# EBN_WPWR_V01.net
KiCad netlist of a schematic drawn in EAGLE
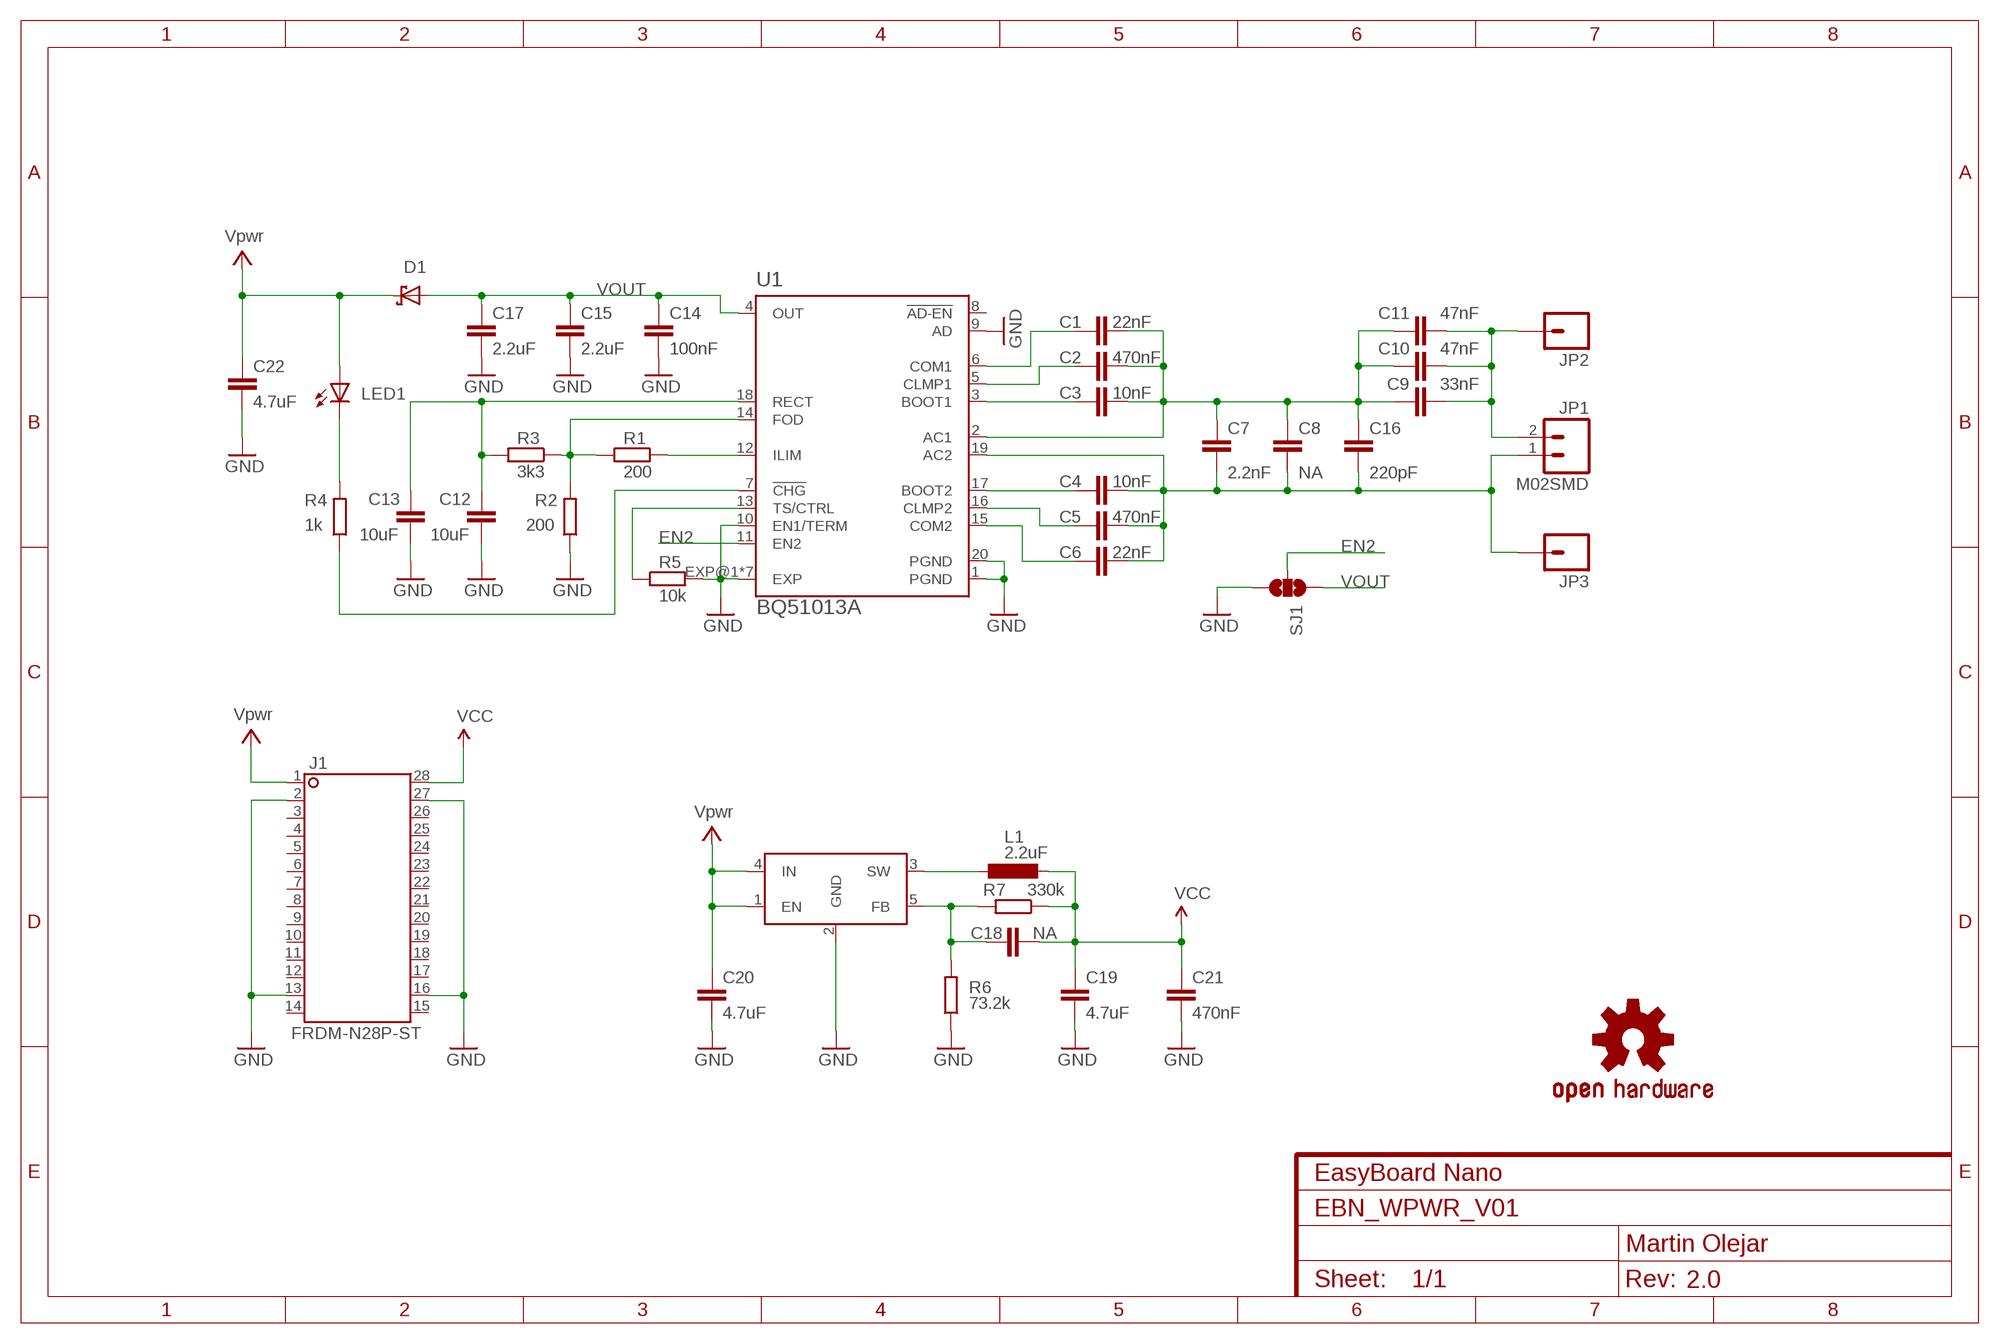
[diagram p0: schematic, sheet 1]

(export (version "E")
  (design (tool "Eeschema 10.0.6"))
  (components
    (comp (ref "C1")
      (value "22nF")
      (footprint "eagle-import:C0603")
      (libsource (lib "eagle-import") (part "C-EUC0603"))
    )
    (comp (ref "C2")
      (value "470nF")
      (footprint "eagle-import:C0603")
      (libsource (lib "eagle-import") (part "C-EUC0603"))
    )
    (comp (ref "C3")
      (value "10nF")
      (footprint "eagle-import:C0603")
      (libsource (lib "eagle-import") (part "C-EUC0603"))
    )
    (comp (ref "C4")
      (value "10nF")
      (footprint "eagle-import:C0603")
      (libsource (lib "eagle-import") (part "C-EUC0603"))
    )
    (comp (ref "C5")
      (value "470nF")
      (footprint "eagle-import:C0603")
      (libsource (lib "eagle-import") (part "C-EUC0603"))
    )
    (comp (ref "C6")
      (value "22nF")
      (footprint "eagle-import:C0603")
      (libsource (lib "eagle-import") (part "C-EUC0603"))
    )
    (comp (ref "C7")
      (value "2.2nF")
      (footprint "eagle-import:C0603")
      (libsource (lib "eagle-import") (part "C-EUC0603"))
    )
    (comp (ref "C8")
      (value "NA")
      (footprint "eagle-import:C0603")
      (libsource (lib "eagle-import") (part "C-EUC0603"))
    )
    (comp (ref "C9")
      (value "33nF")
      (footprint "eagle-import:C0603")
      (libsource (lib "eagle-import") (part "C-EUC0603"))
    )
    (comp (ref "C10")
      (value "47nF")
      (footprint "eagle-import:C0603")
      (libsource (lib "eagle-import") (part "C-EUC0603"))
    )
    (comp (ref "C11")
      (value "47nF")
      (footprint "eagle-import:C0603")
      (libsource (lib "eagle-import") (part "C-EUC0603"))
    )
    (comp (ref "C12")
      (value "10uF")
      (footprint "eagle-import:C0805")
      (libsource (lib "eagle-import") (part "C-EUC0805"))
    )
    (comp (ref "C13")
      (value "10uF")
      (footprint "eagle-import:C0805")
      (libsource (lib "eagle-import") (part "C-EUC0805"))
    )
    (comp (ref "C14")
      (value "100nF")
      (footprint "eagle-import:C0603")
      (libsource (lib "eagle-import") (part "C-EUC0603"))
    )
    (comp (ref "C15")
      (value "2.2uF")
      (footprint "eagle-import:C0603")
      (libsource (lib "eagle-import") (part "C-EUC0603"))
    )
    (comp (ref "C16")
      (value "220pF")
      (footprint "eagle-import:C0603")
      (libsource (lib "eagle-import") (part "C-EUC0603"))
    )
    (comp (ref "C17")
      (value "2.2uF")
      (footprint "eagle-import:C0603")
      (libsource (lib "eagle-import") (part "C-EUC0603"))
    )
    (comp (ref "C18")
      (value "NA")
      (footprint "eagle-import:C0603")
      (libsource (lib "eagle-import") (part "C-EUC0603"))
    )
    (comp (ref "C19")
      (value "4.7uF")
      (footprint "eagle-import:C0603")
      (libsource (lib "eagle-import") (part "C-EUC0603"))
    )
    (comp (ref "C20")
      (value "4.7uF")
      (footprint "eagle-import:C0603")
      (libsource (lib "eagle-import") (part "C-EUC0603"))
    )
    (comp (ref "C21")
      (value "470nF")
      (footprint "eagle-import:C0603")
      (libsource (lib "eagle-import") (part "C-EUC0603"))
    )
    (comp (ref "C22")
      (value "4.7uF")
      (footprint "eagle-import:C0603")
      (libsource (lib "eagle-import") (part "C-EUC0603"))
    )
    (comp (ref "D1")
      (value "PMEG2010BER-SHOTTKY-SOD123FL")
      (footprint "eagle-import:SOD-123FL")
      (libsource (lib "eagle-import") (part "-SHOTTKY-SOD123FLPMEG2010BER"))
    )
    (comp (ref "J1")
      (value "FRDM-N28P-ST")
      (footprint "eagle-import:FRDM-N28P-SHIELD")
      (libsource (lib "eagle-import") (part "FRDM-N28P-ST"))
    )
    (comp (ref "JP1")
      (value "M02SMD")
      (footprint "eagle-import:1X02-1.25MM_SMD")
      (libsource (lib "eagle-import") (part "M02SMD"))
    )
    (comp (ref "JP2")
      (value "M01PTH_LONGPAD")
      (footprint "eagle-import:1X01_LONGPAD")
      (libsource (lib "eagle-import") (part "M01PTH_LONGPAD"))
    )
    (comp (ref "JP3")
      (value "M01PTH_LONGPAD")
      (footprint "eagle-import:1X01_LONGPAD")
      (libsource (lib "eagle-import") (part "M01PTH_LONGPAD"))
    )
    (comp (ref "L1")
      (value "2.2uF")
      (footprint "eagle-import:LPS3015")
      (libsource (lib "eagle-import") (part "L-EULPS3015"))
    )
    (comp (ref "LED1")
      (value "LEDCHIPLED_0603")
      (footprint "eagle-import:CHIPLED_0603")
      (libsource (lib "eagle-import") (part "LEDCHIPLED_0603"))
    )
    (comp (ref "LOGO1")
      (value "OSHW-LOGOS")
      (footprint "eagle-import:OSHW-LOGO-S")
      (libsource (lib "eagle-import") (part "OSHW-LOGOS"))
    )
    (comp (ref "R1")
      (value "200")
      (footprint "eagle-import:R0603")
      (libsource (lib "eagle-import") (part "R-EUR0603"))
    )
    (comp (ref "R2")
      (value "200")
      (footprint "eagle-import:R0603")
      (libsource (lib "eagle-import") (part "R-EUR0603"))
    )
    (comp (ref "R3")
      (value "3k3")
      (footprint "eagle-import:R0603")
      (libsource (lib "eagle-import") (part "R-EUR0603"))
    )
    (comp (ref "R4")
      (value "1k")
      (footprint "eagle-import:R0603")
      (libsource (lib "eagle-import") (part "R-EUR0603"))
    )
    (comp (ref "R5")
      (value "10k")
      (footprint "eagle-import:R0603")
      (libsource (lib "eagle-import") (part "R-EUR0603"))
    )
    (comp (ref "R6")
      (value "73.2k")
      (footprint "eagle-import:R0603")
      (libsource (lib "eagle-import") (part "R-EUR0603"))
    )
    (comp (ref "R7")
      (value "330k")
      (footprint "eagle-import:R0603")
      (libsource (lib "eagle-import") (part "R-EUR0603"))
    )
    (comp (ref "SJ1")
      (value "SJ2W-S")
      (footprint "eagle-import:JUMPER-SMD-S2X")
      (libsource (lib "eagle-import") (part "SJ2W-S"))
    )
    (comp (ref "U$1")
      (value "MP215P")
      (footprint "eagle-import:SOT23-5L")
      (libsource (lib "eagle-import") (part "MP215P"))
    )
    (comp (ref "U1")
      (value "BQ51013A")
      (footprint "eagle-import:RHL_R-VQFN-N20")
      (libsource (lib "eagle-import") (part "BQ51013A"))
    )
  )
  (nets
    (net (code "1") (name "/EN2") (class "Default")
      (node (ref "SJ1") (pin "2") (pinfunction "2_2") (pintype "passive"))
      (node (ref "U1") (pin "11") (pinfunction "EN2_11") (pintype "input"))
    )
    (net (code "2") (name "/VOUT") (class "Default")
      (node (ref "C14") (pin "2") (pinfunction "2_2") (pintype "passive"))
      (node (ref "C15") (pin "2") (pinfunction "2_2") (pintype "passive"))
      (node (ref "C17") (pin "2") (pinfunction "2_2") (pintype "passive"))
      (node (ref "D1") (pin "A") (pinfunction "A_A") (pintype "passive"))
      (node (ref "SJ1") (pin "1") (pinfunction "1_1") (pintype "passive"))
      (node (ref "U1") (pin "4") (pinfunction "OUT_4") (pintype "output"))
    )
    (net (code "3") (name "GND") (class "Default")
      (node (ref "C12") (pin "1") (pinfunction "1_1") (pintype "passive"))
      (node (ref "C13") (pin "1") (pinfunction "1_1") (pintype "passive"))
      (node (ref "C14") (pin "1") (pinfunction "1_1") (pintype "passive"))
      (node (ref "C15") (pin "1") (pinfunction "1_1") (pintype "passive"))
      (node (ref "C17") (pin "1") (pinfunction "1_1") (pintype "passive"))
      (node (ref "C19") (pin "1") (pinfunction "1_1") (pintype "passive"))
      (node (ref "C20") (pin "1") (pinfunction "1_1") (pintype "passive"))
      (node (ref "C21") (pin "1") (pinfunction "1_1") (pintype "passive"))
      (node (ref "C22") (pin "1") (pinfunction "1_1") (pintype "passive"))
      (node (ref "J1") (pin "13") (pinfunction "13_13") (pintype "passive"))
      (node (ref "J1") (pin "16") (pinfunction "16_16") (pintype "passive"))
      (node (ref "J1") (pin "2") (pinfunction "2_2") (pintype "passive"))
      (node (ref "J1") (pin "27") (pinfunction "27_27") (pintype "passive"))
      (node (ref "R2") (pin "1") (pinfunction "1_1") (pintype "passive"))
      (node (ref "R5") (pin "2") (pinfunction "2_2") (pintype "passive"))
      (node (ref "R6") (pin "1") (pinfunction "1_1") (pintype "passive"))
      (node (ref "SJ1") (pin "3") (pinfunction "3_3") (pintype "passive"))
      (node (ref "U$1") (pin "2") (pinfunction "GND_2") (pintype "power_in"))
      (node (ref "U1") (pin "1") (pinfunction "PGND_1") (pintype "power_in"))
      (node (ref "U1") (pin "10") (pinfunction "EN1/TERM_10") (pintype "input"))
      (node (ref "U1") (pin "20") (pinfunction "PGND_20") (pintype "power_in"))
      (node (ref "U1") (pin "9") (pinfunction "AD_9") (pintype "input"))
      (node (ref "U1") (pin "EXP@1") (pinfunction "EXP_EXP@1") (pintype "passive"))
      (node (ref "U1") (pin "EXP@2") (pinfunction "EXP_EXP@2") (pintype "passive"))
      (node (ref "U1") (pin "EXP@3") (pinfunction "EXP_EXP@3") (pintype "passive"))
      (node (ref "U1") (pin "EXP@4") (pinfunction "EXP_EXP@4") (pintype "passive"))
      (node (ref "U1") (pin "EXP@5") (pinfunction "EXP_EXP@5") (pintype "passive"))
      (node (ref "U1") (pin "EXP@6") (pinfunction "EXP_EXP@6") (pintype "passive"))
      (node (ref "U1") (pin "EXP@7") (pinfunction "EXP_EXP@7") (pintype "passive"))
    )
    (net (code "4") (name "Net-(C10-Pad1)") (class "Default")
      (node (ref "C10") (pin "1") (pinfunction "1_1") (pintype "passive"))
      (node (ref "C11") (pin "1") (pinfunction "1_1") (pintype "passive"))
      (node (ref "C9") (pin "1") (pinfunction "1_1") (pintype "passive"))
      (node (ref "JP1") (pin "2") (pinfunction "2_2") (pintype "passive"))
      (node (ref "JP2") (pin "1") (pinfunction "1_1") (pintype "passive"))
    )
    (net (code "5") (name "Net-(L1-1)") (class "Default")
      (node (ref "L1") (pin "P$1") (pinfunction "1_P$1") (pintype "passive"))
      (node (ref "U$1") (pin "3") (pinfunction "SW_3") (pintype "power_in"))
    )
    (net (code "6") (name "Net-(LED1-PadC)") (class "Default")
      (node (ref "LED1") (pin "C") (pinfunction "C_C") (pintype "passive"))
      (node (ref "R4") (pin "2") (pinfunction "2_2") (pintype "passive"))
    )
    (net (code "7") (name "Net-(U$1-FB)") (class "Default")
      (node (ref "C18") (pin "2") (pinfunction "2_2") (pintype "passive"))
      (node (ref "R6") (pin "2") (pinfunction "2_2") (pintype "passive"))
      (node (ref "R7") (pin "2") (pinfunction "2_2") (pintype "passive"))
      (node (ref "U$1") (pin "5") (pinfunction "FB_5") (pintype "input"))
    )
    (net (code "8") (name "Net-(U1-AC1)") (class "Default")
      (node (ref "C1") (pin "2") (pinfunction "2_2") (pintype "passive"))
      (node (ref "C10") (pin "2") (pinfunction "2_2") (pintype "passive"))
      (node (ref "C11") (pin "2") (pinfunction "2_2") (pintype "passive"))
      (node (ref "C16") (pin "2") (pinfunction "2_2") (pintype "passive"))
      (node (ref "C2") (pin "2") (pinfunction "2_2") (pintype "passive"))
      (node (ref "C3") (pin "2") (pinfunction "2_2") (pintype "passive"))
      (node (ref "C7") (pin "2") (pinfunction "2_2") (pintype "passive"))
      (node (ref "C8") (pin "2") (pinfunction "2_2") (pintype "passive"))
      (node (ref "C9") (pin "2") (pinfunction "2_2") (pintype "passive"))
      (node (ref "U1") (pin "2") (pinfunction "AC1_2") (pintype "passive"))
    )
    (net (code "9") (name "Net-(U1-AC2)") (class "Default")
      (node (ref "C16") (pin "1") (pinfunction "1_1") (pintype "passive"))
      (node (ref "C4") (pin "2") (pinfunction "2_2") (pintype "passive"))
      (node (ref "C5") (pin "2") (pinfunction "2_2") (pintype "passive"))
      (node (ref "C6") (pin "2") (pinfunction "2_2") (pintype "passive"))
      (node (ref "C7") (pin "1") (pinfunction "1_1") (pintype "passive"))
      (node (ref "C8") (pin "1") (pinfunction "1_1") (pintype "passive"))
      (node (ref "JP1") (pin "1") (pinfunction "1_1") (pintype "passive"))
      (node (ref "JP3") (pin "1") (pinfunction "1_1") (pintype "passive"))
      (node (ref "U1") (pin "19") (pinfunction "AC2_19") (pintype "passive"))
    )
    (net (code "10") (name "Net-(U1-BOOT1)") (class "Default")
      (node (ref "C3") (pin "1") (pinfunction "1_1") (pintype "passive"))
      (node (ref "U1") (pin "3") (pinfunction "BOOT1_3") (pintype "bidirectional"))
    )
    (net (code "11") (name "Net-(U1-BOOT2)") (class "Default")
      (node (ref "C4") (pin "1") (pinfunction "1_1") (pintype "passive"))
      (node (ref "U1") (pin "17") (pinfunction "BOOT2_17") (pintype "bidirectional"))
    )
    (net (code "12") (name "Net-(U1-CLMP1)") (class "Default")
      (node (ref "C2") (pin "1") (pinfunction "1_1") (pintype "passive"))
      (node (ref "U1") (pin "5") (pinfunction "CLMP1_5") (pintype "bidirectional"))
    )
    (net (code "13") (name "Net-(U1-CLMP2)") (class "Default")
      (node (ref "C5") (pin "1") (pinfunction "1_1") (pintype "passive"))
      (node (ref "U1") (pin "16") (pinfunction "CLMP2_16") (pintype "bidirectional"))
    )
    (net (code "14") (name "Net-(U1-COM1)") (class "Default")
      (node (ref "C1") (pin "1") (pinfunction "1_1") (pintype "passive"))
      (node (ref "U1") (pin "6") (pinfunction "COM1_6") (pintype "bidirectional"))
    )
    (net (code "15") (name "Net-(U1-COM2)") (class "Default")
      (node (ref "C6") (pin "1") (pinfunction "1_1") (pintype "passive"))
      (node (ref "U1") (pin "15") (pinfunction "COM2_15") (pintype "bidirectional"))
    )
    (net (code "16") (name "Net-(U1-FOD)") (class "Default")
      (node (ref "R1") (pin "1") (pinfunction "1_1") (pintype "passive"))
      (node (ref "R2") (pin "2") (pinfunction "2_2") (pintype "passive"))
      (node (ref "R3") (pin "1") (pinfunction "1_1") (pintype "passive"))
      (node (ref "U1") (pin "14") (pinfunction "FOD_14") (pintype "bidirectional"))
    )
    (net (code "17") (name "Net-(U1-ILIM)") (class "Default")
      (node (ref "R1") (pin "2") (pinfunction "2_2") (pintype "passive"))
      (node (ref "U1") (pin "12") (pinfunction "ILIM_12") (pintype "input"))
    )
    (net (code "18") (name "Net-(U1-RECT)") (class "Default")
      (node (ref "C12") (pin "2") (pinfunction "2_2") (pintype "passive"))
      (node (ref "C13") (pin "2") (pinfunction "2_2") (pintype "passive"))
      (node (ref "R3") (pin "2") (pinfunction "2_2") (pintype "passive"))
      (node (ref "U1") (pin "18") (pinfunction "RECT_18") (pintype "output"))
    )
    (net (code "19") (name "Net-(U1-TS{slash}CTRL)") (class "Default")
      (node (ref "R5") (pin "1") (pinfunction "1_1") (pintype "passive"))
      (node (ref "U1") (pin "13") (pinfunction "TS/CTRL_13") (pintype "bidirectional"))
    )
    (net (code "20") (name "Net-(U1-~{CHG})") (class "Default")
      (node (ref "R4") (pin "1") (pinfunction "1_1") (pintype "passive"))
      (node (ref "U1") (pin "7") (pinfunction "~{CHG}_7") (pintype "output"))
    )
    (net (code "21") (name "VCC") (class "Default")
      (node (ref "C18") (pin "1") (pinfunction "1_1") (pintype "passive"))
      (node (ref "C19") (pin "2") (pinfunction "2_2") (pintype "passive"))
      (node (ref "C21") (pin "2") (pinfunction "2_2") (pintype "passive"))
      (node (ref "J1") (pin "28") (pinfunction "28_28") (pintype "passive"))
      (node (ref "L1") (pin "P$2") (pinfunction "2_P$2") (pintype "passive"))
      (node (ref "R7") (pin "1") (pinfunction "1_1") (pintype "passive"))
    )
    (net (code "22") (name "Vpwr") (class "Default")
      (node (ref "C20") (pin "2") (pinfunction "2_2") (pintype "passive"))
      (node (ref "C22") (pin "2") (pinfunction "2_2") (pintype "passive"))
      (node (ref "D1") (pin "C") (pinfunction "C_C") (pintype "passive"))
      (node (ref "J1") (pin "1") (pinfunction "1_1") (pintype "passive"))
      (node (ref "LED1") (pin "A") (pinfunction "A_A") (pintype "passive"))
      (node (ref "U$1") (pin "1") (pinfunction "EN_1") (pintype "input"))
      (node (ref "U$1") (pin "4") (pinfunction "IN_4") (pintype "power_in"))
    )
    (net (code "23") (name "unconnected-(J1-Pad3)") (class "Default")
      (node (ref "J1") (pin "3") (pinfunction "3_3") (pintype "passive"))
    )
    (net (code "24") (name "unconnected-(J1-Pad4)") (class "Default")
      (node (ref "J1") (pin "4") (pinfunction "4_4") (pintype "passive"))
    )
    (net (code "25") (name "unconnected-(J1-Pad5)") (class "Default")
      (node (ref "J1") (pin "5") (pinfunction "5_5") (pintype "passive"))
    )
    (net (code "26") (name "unconnected-(J1-Pad6)") (class "Default")
      (node (ref "J1") (pin "6") (pinfunction "6_6") (pintype "passive"))
    )
    (net (code "27") (name "unconnected-(J1-Pad7)") (class "Default")
      (node (ref "J1") (pin "7") (pinfunction "7_7") (pintype "passive"))
    )
    (net (code "28") (name "unconnected-(J1-Pad8)") (class "Default")
      (node (ref "J1") (pin "8") (pinfunction "8_8") (pintype "passive"))
    )
    (net (code "29") (name "unconnected-(J1-Pad9)") (class "Default")
      (node (ref "J1") (pin "9") (pinfunction "9_9") (pintype "passive"))
    )
    (net (code "30") (name "unconnected-(J1-Pad10)") (class "Default")
      (node (ref "J1") (pin "10") (pinfunction "10_10") (pintype "passive"))
    )
    (net (code "31") (name "unconnected-(J1-Pad11)") (class "Default")
      (node (ref "J1") (pin "11") (pinfunction "11_11") (pintype "passive"))
    )
    (net (code "32") (name "unconnected-(J1-Pad12)") (class "Default")
      (node (ref "J1") (pin "12") (pinfunction "12_12") (pintype "passive"))
    )
    (net (code "33") (name "unconnected-(J1-Pad14)") (class "Default")
      (node (ref "J1") (pin "14") (pinfunction "14_14") (pintype "passive"))
    )
    (net (code "34") (name "unconnected-(J1-Pad15)") (class "Default")
      (node (ref "J1") (pin "15") (pinfunction "15_15") (pintype "passive"))
    )
    (net (code "35") (name "unconnected-(J1-Pad17)") (class "Default")
      (node (ref "J1") (pin "17") (pinfunction "17_17") (pintype "passive"))
    )
    (net (code "36") (name "unconnected-(J1-Pad18)") (class "Default")
      (node (ref "J1") (pin "18") (pinfunction "18_18") (pintype "passive"))
    )
    (net (code "37") (name "unconnected-(J1-Pad19)") (class "Default")
      (node (ref "J1") (pin "19") (pinfunction "19_19") (pintype "passive"))
    )
    (net (code "38") (name "unconnected-(J1-Pad20)") (class "Default")
      (node (ref "J1") (pin "20") (pinfunction "20_20") (pintype "passive"))
    )
    (net (code "39") (name "unconnected-(J1-Pad21)") (class "Default")
      (node (ref "J1") (pin "21") (pinfunction "21_21") (pintype "passive"))
    )
    (net (code "40") (name "unconnected-(J1-Pad22)") (class "Default")
      (node (ref "J1") (pin "22") (pinfunction "22_22") (pintype "passive"))
    )
    (net (code "41") (name "unconnected-(J1-Pad23)") (class "Default")
      (node (ref "J1") (pin "23") (pinfunction "23_23") (pintype "passive"))
    )
    (net (code "42") (name "unconnected-(J1-Pad24)") (class "Default")
      (node (ref "J1") (pin "24") (pinfunction "24_24") (pintype "passive"))
    )
    (net (code "43") (name "unconnected-(J1-Pad25)") (class "Default")
      (node (ref "J1") (pin "25") (pinfunction "25_25") (pintype "passive"))
    )
    (net (code "44") (name "unconnected-(J1-Pad26)") (class "Default")
      (node (ref "J1") (pin "26") (pinfunction "26_26") (pintype "passive"))
    )
    (net (code "45") (name "unconnected-(U1-~{AD-EN}-Pad8)") (class "Default")
      (node (ref "U1") (pin "8") (pinfunction "~{AD-EN}_8") (pintype "output"))
    )
  )
)
